# 05021002_PWM_-_Buzzer_and_Led.net
KiCad netlist of a schematic drawn in Altium Designer
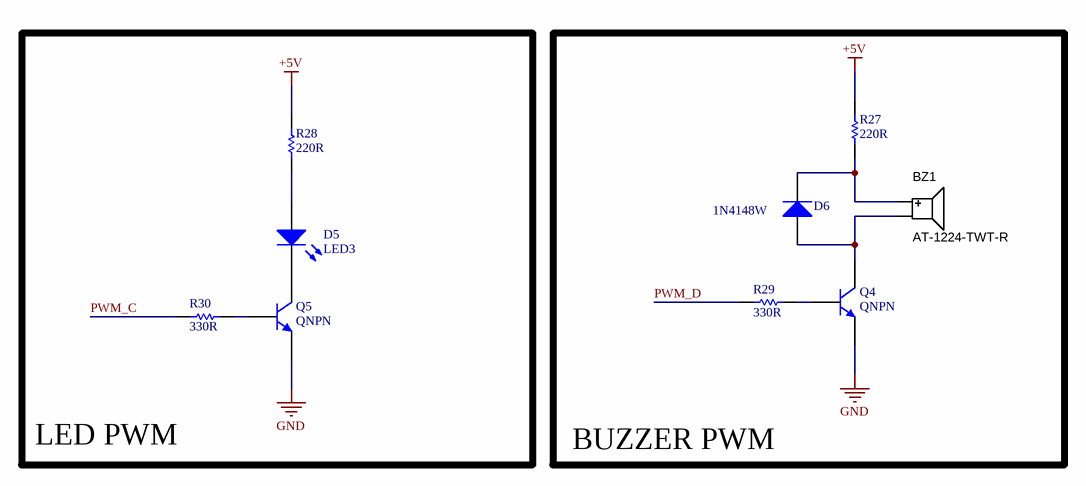
[diagram p0: 05021002_PWM - Buzzer and Led.SchDoc]

(export (version "E")
  (design (tool "Eeschema 10.0.6"))
  (components
    (comp (ref "BZ1")
      (value "5V BUZZER")
      (footprint "BUZZER_12.0X8.5MM")
      (description "Speaker, Magnetic Transducer")
      (fields (field (name "PART NUMBER 1") "AT-1224-TWT-R"))
      (libsource (lib "PBL - Electromechanical") (part "BZ_12x8.5x6.5_2kHz"))
    )
    (comp (ref "D5")
      (value "LED3")
      (footprint "LED-0805-K")
      (description "Typical BLUE SiC LED")
      (fields (field (name "PUBLISHER") "Altium Limited"))
      (libsource (lib "Miscellaneous Devices") (part "LED3"))
    )
    (comp (ref "D6")
      (value "1N4148W")
      (footprint "SOD-123")
      (description "Small Signal Fast Switching Diode")
      (libsource (lib "PROJ_SENSOMASTHER") (part "1N4148W"))
    )
    (comp (ref "Q4")
      (value "QNPN")
      (footprint "SOT-23")
      (description "NPN Bipolar Transistor")
      (fields (field (name "PUBLISHER") "Altium Limited"))
      (libsource (lib "Miscellaneous Devices") (part "QNPN"))
    )
    (comp (ref "Q5")
      (value "QNPN")
      (footprint "SOT-23")
      (description "NPN Bipolar Transistor")
      (fields (field (name "PUBLISHER") "Altium Limited"))
      (libsource (lib "Miscellaneous Devices") (part "QNPN"))
    )
    (comp (ref "R27")
      (value "220R")
      (footprint "0805")
      (libsource (lib "resistor_smd_gen") (part "resistor_gen"))
    )
    (comp (ref "R28")
      (value "220R")
      (footprint "0805")
      (libsource (lib "resistor_smd_gen") (part "resistor_gen"))
    )
    (comp (ref "R29")
      (value "330R")
      (footprint "0805")
      (libsource (lib "resistor_smd_gen") (part "resistor_gen"))
    )
    (comp (ref "R30")
      (value "330R")
      (footprint "0805")
      (libsource (lib "resistor_smd_gen") (part "resistor_gen"))
    )
  )
  (nets
    (net (code "1") (name "+5V") (class "Default")
      (node (ref "R27") (pin "2") (pinfunction "2_2") (pintype "passive"))
      (node (ref "R28") (pin "2") (pinfunction "2_2") (pintype "passive"))
    )
    (net (code "2") (name "/PWM_C") (class "Default")
      (node (ref "R30") (pin "1") (pinfunction "1_1") (pintype "passive"))
    )
    (net (code "3") (name "/PWM_D") (class "Default")
      (node (ref "R29") (pin "1") (pinfunction "1_1") (pintype "passive"))
    )
    (net (code "4") (name "GND") (class "Default")
      (node (ref "Q4") (pin "3") (pinfunction "E_3") (pintype "passive"))
      (node (ref "Q5") (pin "3") (pinfunction "E_3") (pintype "passive"))
    )
    (net (code "5") (name "Net-(BZ1-Negative)") (class "Default")
      (node (ref "BZ1") (pin "2") (pinfunction "Negative_2") (pintype "passive"))
      (node (ref "D6") (pin "2") (pinfunction "A_2") (pintype "passive"))
      (node (ref "Q4") (pin "1") (pinfunction "C_1") (pintype "passive"))
    )
    (net (code "6") (name "Net-(BZ1-Positive)") (class "Default")
      (node (ref "BZ1") (pin "1") (pinfunction "Positive_1") (pintype "passive"))
      (node (ref "D6") (pin "1") (pinfunction "K_1") (pintype "passive"))
      (node (ref "R27") (pin "1") (pinfunction "1_1") (pintype "passive"))
    )
    (net (code "7") (name "Net-(D5-A)") (class "Default")
      (node (ref "D5") (pin "1") (pinfunction "A_1") (pintype "passive"))
      (node (ref "R28") (pin "1") (pinfunction "1_1") (pintype "passive"))
    )
    (net (code "8") (name "Net-(D5-K)") (class "Default")
      (node (ref "D5") (pin "2") (pinfunction "K_2") (pintype "passive"))
      (node (ref "Q5") (pin "1") (pinfunction "C_1") (pintype "passive"))
    )
    (net (code "9") (name "Net-(Q4-B)") (class "Default")
      (node (ref "Q4") (pin "2") (pinfunction "B_2") (pintype "passive"))
      (node (ref "R29") (pin "2") (pinfunction "2_2") (pintype "passive"))
    )
    (net (code "10") (name "Net-(Q5-B)") (class "Default")
      (node (ref "Q5") (pin "2") (pinfunction "B_2") (pintype "passive"))
      (node (ref "R30") (pin "2") (pinfunction "2_2") (pintype "passive"))
    )
  )
)
